# poe-assembly.net
KiCad netlist of a schematic drawn in EAGLE
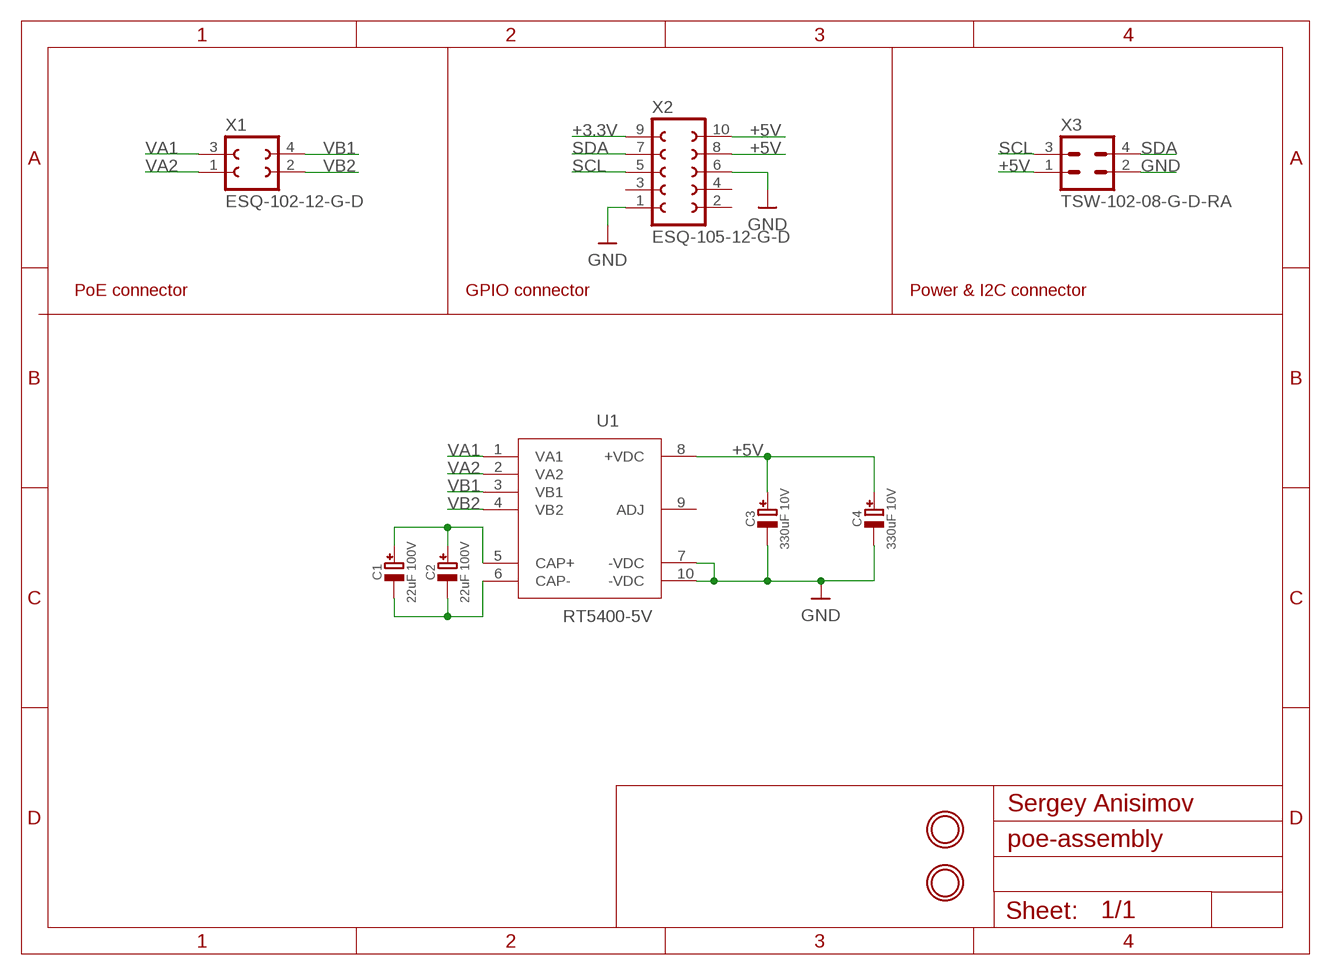
[diagram p0: schematic, sheet 1]

(export (version "E")
  (design (tool "Eeschema 10.0.6"))
  (components
    (comp (ref "C1")
      (value "22uF 100V")
      (footprint "eagle-import:CAP-PRD250-W50-D630")
      (libsource (lib "eagle-import") (part "CAPACITOR_POLCAP-PRD250-W50-D630"))
    )
    (comp (ref "C2")
      (value "22uF 100V")
      (footprint "eagle-import:CAP-PRD250-W50-D630")
      (libsource (lib "eagle-import") (part "CAPACITOR_POLCAP-PRD250-W50-D630"))
    )
    (comp (ref "C3")
      (value "330uF 10V")
      (footprint "eagle-import:CAP-PRD250-W50-D630")
      (libsource (lib "eagle-import") (part "CAPACITOR_POLCAP-PRD250-W50-D630"))
    )
    (comp (ref "C4")
      (value "330uF 10V")
      (footprint "eagle-import:CAP-PRD250-W50-D630")
      (libsource (lib "eagle-import") (part "CAPACITOR_POLCAP-PRD250-W50-D630"))
    )
    (comp (ref "U$6")
      (value "MOUNTING-HOLE2.7_THICK")
      (footprint "eagle-import:MOUNTINGHOLE_2.7_PLATED_THICK")
      (libsource (lib "eagle-import") (part "MOUNTING-HOLE2.7_THICK"))
    )
    (comp (ref "U$7")
      (value "MOUNTING-HOLE2.7_THICK")
      (footprint "eagle-import:MOUNTINGHOLE_2.7_PLATED_THICK")
      (libsource (lib "eagle-import") (part "MOUNTING-HOLE2.7_THICK"))
    )
    (comp (ref "U1")
      (value "RT5400-5V")
      (footprint "eagle-import:MODULE-RT5400")
      (libsource (lib "eagle-import") (part "MODULE-RT5400"))
    )
    (comp (ref "X1")
      (value "ESQ-102-12-G-D")
      (footprint "eagle-import:ESQ-102-D")
      (libsource (lib "eagle-import") (part "CON-FE-02-02ESQ-102-12-S-D"))
    )
    (comp (ref "X2")
      (value "ESQ-105-12-G-D")
      (footprint "eagle-import:ESQ-105-D")
      (libsource (lib "eagle-import") (part "CON-FE-05-02ESQ-105-12-S-D"))
    )
    (comp (ref "X3")
      (value "TSW-102-08-G-D-RA")
      (footprint "eagle-import:TSW-102-D-RA")
      (libsource (lib "eagle-import") (part "CON-MA-02-02"))
    )
  )
  (nets
    (net (code "1") (name "/+3.3V") (class "Default")
      (node (ref "X2") (pin "9") (pinfunction "9_9") (pintype "passive"))
    )
    (net (code "2") (name "/+5V") (class "Default")
      (node (ref "C3") (pin "1") (pinfunction "+_1") (pintype "passive"))
      (node (ref "C4") (pin "1") (pinfunction "+_1") (pintype "passive"))
      (node (ref "U1") (pin "8") (pinfunction "+VDC_8") (pintype "bidirectional"))
      (node (ref "X2") (pin "10") (pinfunction "10_10") (pintype "passive"))
      (node (ref "X2") (pin "8") (pinfunction "8_8") (pintype "passive"))
      (node (ref "X3") (pin "1") (pinfunction "1_1") (pintype "passive"))
    )
    (net (code "3") (name "/SCL") (class "Default")
      (node (ref "X2") (pin "5") (pinfunction "5_5") (pintype "passive"))
      (node (ref "X3") (pin "3") (pinfunction "3_3") (pintype "passive"))
    )
    (net (code "4") (name "/SDA") (class "Default")
      (node (ref "X2") (pin "7") (pinfunction "7_7") (pintype "passive"))
      (node (ref "X3") (pin "4") (pinfunction "4_4") (pintype "passive"))
    )
    (net (code "5") (name "/VA1") (class "Default")
      (node (ref "U1") (pin "1") (pinfunction "VA1_1") (pintype "bidirectional"))
      (node (ref "X1") (pin "3") (pinfunction "3_3") (pintype "passive"))
    )
    (net (code "6") (name "/VA2") (class "Default")
      (node (ref "U1") (pin "2") (pinfunction "VA2_2") (pintype "bidirectional"))
      (node (ref "X1") (pin "1") (pinfunction "1_1") (pintype "passive"))
    )
    (net (code "7") (name "/VB1") (class "Default")
      (node (ref "U1") (pin "3") (pinfunction "VB1_3") (pintype "bidirectional"))
      (node (ref "X1") (pin "4") (pinfunction "4_4") (pintype "passive"))
    )
    (net (code "8") (name "/VB2") (class "Default")
      (node (ref "U1") (pin "4") (pinfunction "VB2_4") (pintype "bidirectional"))
      (node (ref "X1") (pin "2") (pinfunction "2_2") (pintype "passive"))
    )
    (net (code "9") (name "GND") (class "Default")
      (node (ref "C3") (pin "2") (pinfunction "-_2") (pintype "passive"))
      (node (ref "C4") (pin "2") (pinfunction "-_2") (pintype "passive"))
      (node (ref "U1") (pin "10") (pinfunction "-VDC_10") (pintype "bidirectional"))
      (node (ref "U1") (pin "7") (pinfunction "-VDC_7") (pintype "bidirectional"))
      (node (ref "X2") (pin "1") (pinfunction "1_1") (pintype "passive"))
      (node (ref "X2") (pin "6") (pinfunction "6_6") (pintype "passive"))
      (node (ref "X3") (pin "2") (pinfunction "2_2") (pintype "passive"))
    )
    (net (code "10") (name "Net-(C1-+)") (class "Default")
      (node (ref "C1") (pin "1") (pinfunction "+_1") (pintype "passive"))
      (node (ref "C2") (pin "1") (pinfunction "+_1") (pintype "passive"))
      (node (ref "U1") (pin "5") (pinfunction "CAP+_5") (pintype "bidirectional"))
    )
    (net (code "11") (name "Net-(C1--)") (class "Default")
      (node (ref "C1") (pin "2") (pinfunction "-_2") (pintype "passive"))
      (node (ref "C2") (pin "2") (pinfunction "-_2") (pintype "passive"))
      (node (ref "U1") (pin "6") (pinfunction "CAP-_6") (pintype "bidirectional"))
    )
    (net (code "12") (name "unconnected-(U1-ADJ-Pad9)") (class "Default")
      (node (ref "U1") (pin "9") (pinfunction "ADJ_9") (pintype "bidirectional"))
    )
    (net (code "13") (name "unconnected-(X2-Pad2)") (class "Default")
      (node (ref "X2") (pin "2") (pinfunction "2_2") (pintype "passive"))
    )
    (net (code "14") (name "unconnected-(X2-Pad3)") (class "Default")
      (node (ref "X2") (pin "3") (pinfunction "3_3") (pintype "passive"))
    )
    (net (code "15") (name "unconnected-(X2-Pad4)") (class "Default")
      (node (ref "X2") (pin "4") (pinfunction "4_4") (pintype "passive"))
    )
  )
)
